# Adafruit_Metro_RP2040.net
KiCad netlist of a schematic drawn in EAGLE
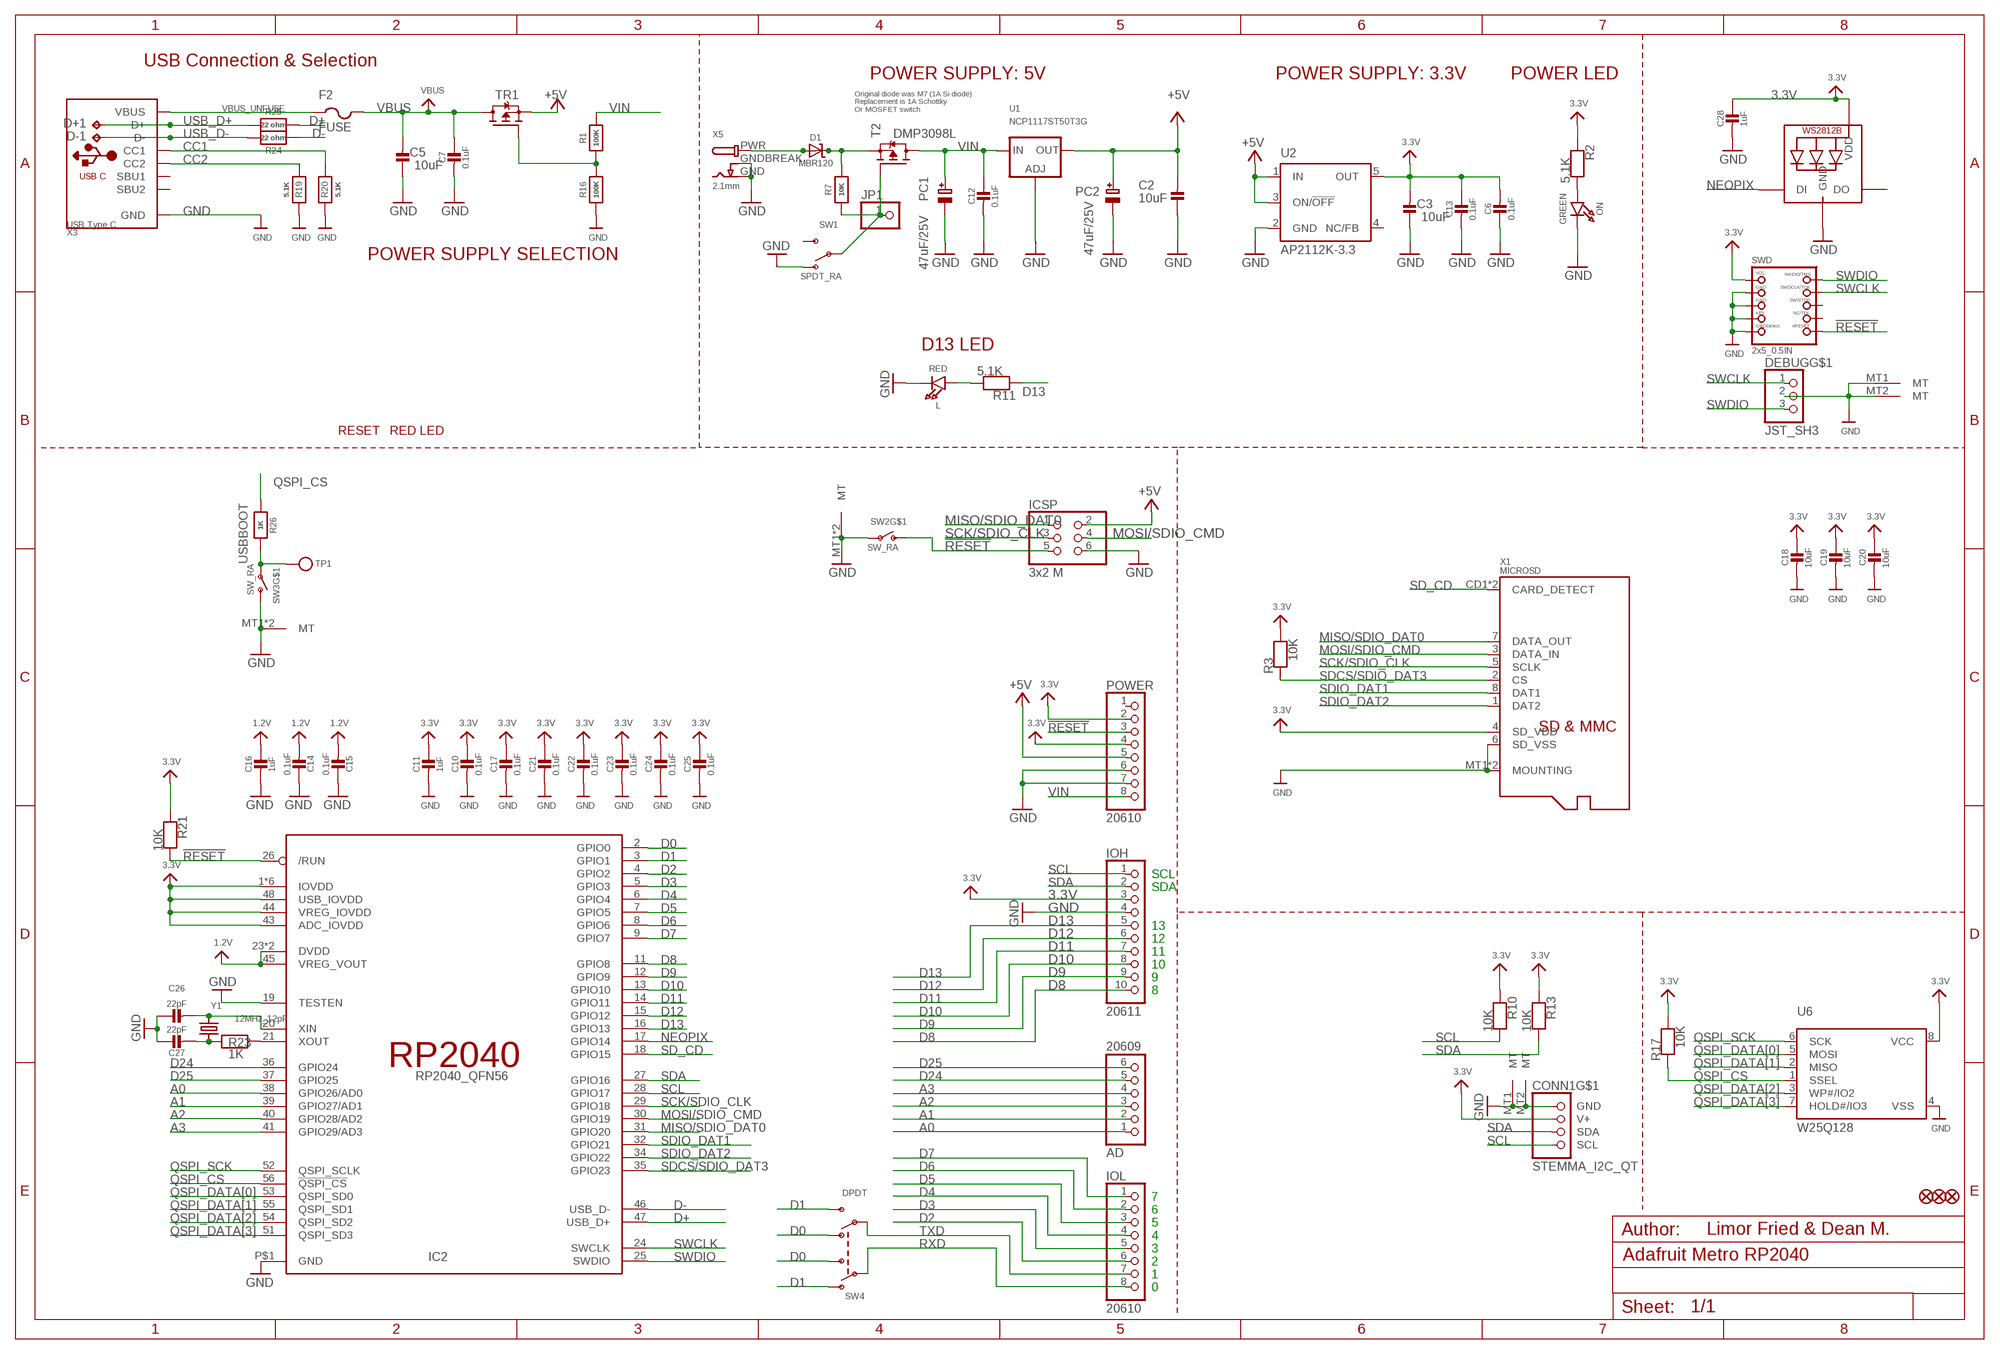
[diagram p0: schematic, sheet 1]

(export (version "E")
  (design (tool "Eeschema 10.0.6"))
  (components
    (comp (ref "AD")
      (value "20609")
      (footprint "eagle-import:1X06_OVALWAVE")
      (libsource (lib "eagle-import") (part "HEADER-1X6OVALWAVE"))
    )
    (comp (ref "C2")
      (value "10uF")
      (footprint "eagle-import:0805-NO")
      (libsource (lib "eagle-import") (part "CAP_CERAMIC0805-NOOUTLINE"))
    )
    (comp (ref "C3")
      (value "10uF")
      (footprint "eagle-import:0805-NO")
      (libsource (lib "eagle-import") (part "CAP_CERAMIC0805-NOOUTLINE"))
    )
    (comp (ref "C5")
      (value "10uF")
      (footprint "eagle-import:0805-NO")
      (libsource (lib "eagle-import") (part "CAP_CERAMIC0805-NOOUTLINE"))
    )
    (comp (ref "C6")
      (value "0.1uF")
      (footprint "eagle-import:0603-NO")
      (libsource (lib "eagle-import") (part "CAP_CERAMIC0603_NO"))
    )
    (comp (ref "C7")
      (value "0.1uF")
      (footprint "eagle-import:0603-NO")
      (libsource (lib "eagle-import") (part "CAP_CERAMIC0603_NO"))
    )
    (comp (ref "C10")
      (value "0.1uF")
      (footprint "eagle-import:0603-NO")
      (libsource (lib "eagle-import") (part "CAP_CERAMIC0603_NO"))
    )
    (comp (ref "C11")
      (value "1uF")
      (footprint "eagle-import:0603-NO")
      (libsource (lib "eagle-import") (part "CAP_CERAMIC0603_NO"))
    )
    (comp (ref "C12")
      (value "0.1uF")
      (footprint "eagle-import:0603-NO")
      (libsource (lib "eagle-import") (part "CAP_CERAMIC0603_NO"))
    )
    (comp (ref "C13")
      (value "0.1uF")
      (footprint "eagle-import:0603-NO")
      (libsource (lib "eagle-import") (part "CAP_CERAMIC0603_NO"))
    )
    (comp (ref "C14")
      (value "0.1uF")
      (footprint "eagle-import:0603-NO")
      (libsource (lib "eagle-import") (part "CAP_CERAMIC0603_NO"))
    )
    (comp (ref "C15")
      (value "0.1uF")
      (footprint "eagle-import:0603-NO")
      (libsource (lib "eagle-import") (part "CAP_CERAMIC0603_NO"))
    )
    (comp (ref "C16")
      (value "1uF")
      (footprint "eagle-import:0603-NO")
      (libsource (lib "eagle-import") (part "CAP_CERAMIC0603_NO"))
    )
    (comp (ref "C17")
      (value "0.1uF")
      (footprint "eagle-import:0603-NO")
      (libsource (lib "eagle-import") (part "CAP_CERAMIC0603_NO"))
    )
    (comp (ref "C18")
      (value "10uF")
      (footprint "eagle-import:0805-NO")
      (libsource (lib "eagle-import") (part "CAP_CERAMIC0805-NOOUTLINE"))
    )
    (comp (ref "C19")
      (value "10uF")
      (footprint "eagle-import:0805-NO")
      (libsource (lib "eagle-import") (part "CAP_CERAMIC0805-NOOUTLINE"))
    )
    (comp (ref "C20")
      (value "10uF")
      (footprint "eagle-import:0805-NO")
      (libsource (lib "eagle-import") (part "CAP_CERAMIC0805-NOOUTLINE"))
    )
    (comp (ref "C21")
      (value "0.1uF")
      (footprint "eagle-import:0603-NO")
      (libsource (lib "eagle-import") (part "CAP_CERAMIC0603_NO"))
    )
    (comp (ref "C22")
      (value "0.1uF")
      (footprint "eagle-import:0603-NO")
      (libsource (lib "eagle-import") (part "CAP_CERAMIC0603_NO"))
    )
    (comp (ref "C23")
      (value "0.1uF")
      (footprint "eagle-import:0603-NO")
      (libsource (lib "eagle-import") (part "CAP_CERAMIC0603_NO"))
    )
    (comp (ref "C24")
      (value "0.1uF")
      (footprint "eagle-import:0603-NO")
      (libsource (lib "eagle-import") (part "CAP_CERAMIC0603_NO"))
    )
    (comp (ref "C25")
      (value "0.1uF")
      (footprint "eagle-import:0603-NO")
      (libsource (lib "eagle-import") (part "CAP_CERAMIC0603_NO"))
    )
    (comp (ref "C26")
      (value "22pF")
      (footprint "eagle-import:0603-NO")
      (libsource (lib "eagle-import") (part "CAP_CERAMIC0603_NO"))
    )
    (comp (ref "C27")
      (value "22pF")
      (footprint "eagle-import:0603-NO")
      (libsource (lib "eagle-import") (part "CAP_CERAMIC0603_NO"))
    )
    (comp (ref "C28")
      (value "1uF")
      (footprint "eagle-import:0603-NO")
      (libsource (lib "eagle-import") (part "CAP_CERAMIC0603_NO"))
    )
    (comp (ref "CONN1")
      (value "STEMMA_I2C_QT")
      (footprint "eagle-import:JST_SH4")
      (libsource (lib "eagle-import") (part "STEMMA_I2C_QT"))
    )
    (comp (ref "D+1")
      (value "TPB1,27")
      (footprint "eagle-import:B1,27")
      (libsource (lib "eagle-import") (part "TPB1,27"))
    )
    (comp (ref "D-1")
      (value "TPB1,27")
      (footprint "eagle-import:B1,27")
      (libsource (lib "eagle-import") (part "TPB1,27"))
    )
    (comp (ref "D1")
      (value "MBR120")
      (footprint "eagle-import:SOD-123")
      (libsource (lib "eagle-import") (part "DIODE-SCHOTTKYSOD-123"))
    )
    (comp (ref "DEBUG")
      (value "JST_SH3")
      (footprint "eagle-import:JST_SH3")
      (libsource (lib "eagle-import") (part "CON_JST_SH_3PINSH"))
    )
    (comp (ref "F2")
      (value "FUSE")
      (footprint "eagle-import:R1206")
      (libsource (lib "eagle-import") (part "PTCFUSE-1206"))
    )
    (comp (ref "FD1")
      (value "FIDUCIAL_1MM")
      (footprint "eagle-import:FIDUCIAL_1MM")
      (libsource (lib "eagle-import") (part "FIDUCIAL_1MM"))
    )
    (comp (ref "FD2")
      (value "FIDUCIAL_1MM")
      (footprint "eagle-import:FIDUCIAL_1MM")
      (libsource (lib "eagle-import") (part "FIDUCIAL_1MM"))
    )
    (comp (ref "FD3")
      (value "FIDUCIAL_1MM")
      (footprint "eagle-import:FIDUCIAL_1MM")
      (libsource (lib "eagle-import") (part "FIDUCIAL_1MM"))
    )
    (comp (ref "IC2")
      (value "RP2040_QFN56")
      (footprint "eagle-import:QFN56_7MM_REDUCEDEPAD")
      (libsource (lib "eagle-import") (part "RP2040_QFN56"))
    )
    (comp (ref "ICSP")
      (value "3x2 M")
      (footprint "eagle-import:2X03_ROUND_70MIL")
      (libsource (lib "eagle-import") (part "HEADER-2X3"))
    )
    (comp (ref "IOH")
      (value "20611")
      (footprint "eagle-import:1X10_OVALWAVE")
      (libsource (lib "eagle-import") (part "HEADER-1X10OVALWAVE"))
    )
    (comp (ref "IOL")
      (value "20610")
      (footprint "eagle-import:1X08_OVALWAVE")
      (libsource (lib "eagle-import") (part "HEADER-1X8OVALWAVE"))
    )
    (comp (ref "JP1")
      (value "HEADER-1X1ROUND")
      (footprint "eagle-import:1X01_ROUND")
      (libsource (lib "eagle-import") (part "HEADER-1X1ROUND"))
    )
    (comp (ref "L")
      (value "RED")
      (footprint "eagle-import:CHIPLED_0603_NOOUTLINE")
      (libsource (lib "eagle-import") (part "LED0603_NOOUTLINE"))
    )
    (comp (ref "LED2")
      (value "WS2812B_3535FULL")
      (footprint "eagle-import:LED3535_FULLPADS")
      (libsource (lib "eagle-import") (part "WS2812B_3535FULL"))
    )
    (comp (ref "ON")
      (value "GREEN")
      (footprint "eagle-import:CHIPLED_0603_NOOUTLINE")
      (libsource (lib "eagle-import") (part "LED0603_NOOUTLINE"))
    )
    (comp (ref "PC1")
      (value "47uF/25V")
      (footprint "eagle-import:PANASONIC_D")
      (libsource (lib "eagle-import") (part "CAP_ELECTROLYTICPANASONIC_D"))
    )
    (comp (ref "PC2")
      (value "47uF/25V")
      (footprint "eagle-import:PANASONIC_D")
      (libsource (lib "eagle-import") (part "CAP_ELECTROLYTICPANASONIC_D"))
    )
    (comp (ref "POWER")
      (value "20610")
      (footprint "eagle-import:1X08_OVALWAVE")
      (libsource (lib "eagle-import") (part "HEADER-1X8OVALWAVE"))
    )
    (comp (ref "R1")
      (value "100K")
      (footprint "eagle-import:0603-NO")
      (libsource (lib "eagle-import") (part "RESISTOR_0603_NOOUT"))
    )
    (comp (ref "R2")
      (value "5.1K")
      (footprint "eagle-import:0603-NO")
      (libsource (lib "eagle-import") (part "RESISTOR_0603_NOOUT"))
    )
    (comp (ref "R3")
      (value "10K")
      (footprint "eagle-import:0603-NO")
      (libsource (lib "eagle-import") (part "RESISTOR_0603_NOOUT"))
    )
    (comp (ref "R7")
      (value "10K")
      (footprint "eagle-import:0603-NO")
      (libsource (lib "eagle-import") (part "RESISTOR_0603_NOOUT"))
    )
    (comp (ref "R10")
      (value "10K")
      (footprint "eagle-import:0603-NO")
      (libsource (lib "eagle-import") (part "RESISTOR_0603_NOOUT"))
    )
    (comp (ref "R11")
      (value "5.1K")
      (footprint "eagle-import:0603-NO")
      (libsource (lib "eagle-import") (part "RESISTOR_0603_NOOUT"))
    )
    (comp (ref "R13")
      (value "10K")
      (footprint "eagle-import:0603-NO")
      (libsource (lib "eagle-import") (part "RESISTOR_0603_NOOUT"))
    )
    (comp (ref "R16")
      (value "100K")
      (footprint "eagle-import:0603-NO")
      (libsource (lib "eagle-import") (part "RESISTOR_0603_NOOUT"))
    )
    (comp (ref "R17")
      (value "10K")
      (footprint "eagle-import:0603-NO")
      (libsource (lib "eagle-import") (part "RESISTOR_0603_NOOUT"))
    )
    (comp (ref "R19")
      (value "5.1K")
      (footprint "eagle-import:0603-NO")
      (libsource (lib "eagle-import") (part "RESISTOR_0603_NOOUT"))
    )
    (comp (ref "R20")
      (value "5.1K")
      (footprint "eagle-import:0603-NO")
      (libsource (lib "eagle-import") (part "RESISTOR_0603_NOOUT"))
    )
    (comp (ref "R21")
      (value "10K")
      (footprint "eagle-import:0603-NO")
      (libsource (lib "eagle-import") (part "RESISTOR_0603_NOOUT"))
    )
    (comp (ref "R23")
      (value "1K")
      (footprint "eagle-import:0603-NO")
      (libsource (lib "eagle-import") (part "RESISTOR_0603_NOOUT"))
    )
    (comp (ref "R24")
      (value "22 ohm")
      (footprint "eagle-import:0603-NO")
      (libsource (lib "eagle-import") (part "RESISTOR_0603_NOOUT"))
    )
    (comp (ref "R25")
      (value "22 ohm")
      (footprint "eagle-import:0603-NO")
      (libsource (lib "eagle-import") (part "RESISTOR_0603_NOOUT"))
    )
    (comp (ref "R26")
      (value "1K")
      (footprint "eagle-import:0603-NO")
      (libsource (lib "eagle-import") (part "RESISTOR_0603_NOOUT"))
    )
    (comp (ref "SW1")
      (value "SPDT_RA")
      (footprint "eagle-import:SPDT_SMT_SSSS811101")
      (libsource (lib "eagle-import") (part "SWITCH_SPDT"))
    )
    (comp (ref "SW2")
      (value "SW_RA")
      (footprint "eagle-import:SPST_TACTILE_RA")
      (libsource (lib "eagle-import") (part "SWITCH_SPST_MNT_TACT_RA"))
    )
    (comp (ref "SW3")
      (value "SW_RA")
      (footprint "eagle-import:SPST_TACTILE_RA")
      (libsource (lib "eagle-import") (part "SWITCH_SPST_MNT_TACT_RA"))
    )
    (comp (ref "SW4")
      (value "DPDT")
      (footprint "eagle-import:EG1390")
      (libsource (lib "eagle-import") (part "SWITCH_DPDTEG1390"))
    )
    (comp (ref "SWD")
      (value "2x5_0.5IN")
      (footprint "eagle-import:2X05_1.27MM_BOX_POSTS")
      (libsource (lib "eagle-import") (part "JTAG-CORTEXBOXPOSTS"))
    )
    (comp (ref "T2")
      (value "DMP3098L")
      (footprint "eagle-import:SOT23-WIDE")
      (libsource (lib "eagle-import") (part "MOSFET-PWIDE"))
    )
    (comp (ref "TP1")
      (value "TESTPOINTROUND1.5MMNO")
      (footprint "eagle-import:TESTPOINT_ROUND_1.5MM_NO")
      (libsource (lib "eagle-import") (part "TESTPOINTROUND1.5MMNO"))
    )
    (comp (ref "TR1")
      (value "DMP3098L")
      (footprint "eagle-import:SOT23-WIDE")
      (libsource (lib "eagle-import") (part "MOSFET-PWIDE"))
    )
    (comp (ref "U1")
      (value "NCP1117ST50T3G")
      (footprint "eagle-import:SOT223-R")
      (libsource (lib "eagle-import") (part "LM1117SOT223-REFLOW"))
    )
    (comp (ref "U2")
      (value "AP2112K-3.3")
      (footprint "eagle-import:SOT23-DBV")
      (libsource (lib "eagle-import") (part "LP2985-XXDBVR33"))
    )
    (comp (ref "U6")
      (value "W25Q128")
      (footprint "eagle-import:SOIC8_208MIL")
      (libsource (lib "eagle-import") (part "SPIFLASH_8PIN208MIL"))
    )
    (comp (ref "X1")
      (value "MICROSD")
      (footprint "eagle-import:MICROSD")
      (libsource (lib "eagle-import") (part "MICROSD"))
    )
    (comp (ref "X3")
      (value "USB Type C")
      (footprint "eagle-import:USB_C_CUSB31-CFM2AX-01-X")
      (libsource (lib "eagle-import") (part "USB_C"))
    )
    (comp (ref "X5")
      (value "2.1mm")
      (footprint "eagle-import:DCJACK_2MM_PTH")
      (libsource (lib "eagle-import") (part "DCBARRELPTH"))
    )
    (comp (ref "Y1")
      (value "12MHz_12pF")
      (footprint "eagle-import:CRYSTAL_2.5X2")
      (libsource (lib "eagle-import") (part "CRYSTAL2.5X2.0"))
    )
  )
  (nets
    (net (code "1") (name "+5V") (class "Default")
      (node (ref "C2") (pin "2") (pinfunction "2_2") (pintype "passive"))
      (node (ref "ICSP") (pin "2") (pinfunction "2_2") (pintype "passive"))
      (node (ref "PC2") (pin "+") (pinfunction "+_+") (pintype "passive"))
      (node (ref "POWER") (pin "5") (pinfunction "5_5") (pintype "passive"))
      (node (ref "TR1") (pin "2") (pinfunction "S_2") (pintype "passive"))
      (node (ref "U1") (pin "2") (pinfunction "OUT_2") (pintype "passive"))
      (node (ref "U1") (pin "4") (pinfunction "OUT_4") (pintype "passive"))
      (node (ref "U2") (pin "1") (pinfunction "IN_1") (pintype "input"))
      (node (ref "U2") (pin "3") (pinfunction "ON/~{OFF}_3") (pintype "input"))
    )
    (net (code "2") (name "/A0") (class "Default")
      (node (ref "AD") (pin "1") (pinfunction "1_1") (pintype "passive"))
      (node (ref "IC2") (pin "38") (pinfunction "GPIO26/AD0_38") (pintype "bidirectional"))
    )
    (net (code "3") (name "/A1") (class "Default")
      (node (ref "AD") (pin "2") (pinfunction "2_2") (pintype "passive"))
      (node (ref "IC2") (pin "39") (pinfunction "GPIO27/AD1_39") (pintype "bidirectional"))
    )
    (net (code "4") (name "/A2") (class "Default")
      (node (ref "AD") (pin "3") (pinfunction "3_3") (pintype "passive"))
      (node (ref "IC2") (pin "40") (pinfunction "GPIO28/AD2_40") (pintype "bidirectional"))
    )
    (net (code "5") (name "/A3") (class "Default")
      (node (ref "AD") (pin "4") (pinfunction "4_4") (pintype "passive"))
      (node (ref "IC2") (pin "41") (pinfunction "GPIO29/AD3_41") (pintype "bidirectional"))
    )
    (net (code "6") (name "/CC1") (class "Default")
      (node (ref "R20") (pin "2") (pinfunction "2_2") (pintype "passive"))
      (node (ref "X3") (pin "A5") (pinfunction "CC1_A5") (pintype "bidirectional"))
    )
    (net (code "7") (name "/CC2") (class "Default")
      (node (ref "R19") (pin "2") (pinfunction "2_2") (pintype "passive"))
      (node (ref "X3") (pin "B5") (pinfunction "CC2_B5") (pintype "bidirectional"))
    )
    (net (code "8") (name "/D+") (class "Default")
      (node (ref "IC2") (pin "47") (pinfunction "USB_D+_47") (pintype "bidirectional"))
      (node (ref "R25") (pin "2") (pinfunction "2_2") (pintype "passive"))
    )
    (net (code "9") (name "/D-") (class "Default")
      (node (ref "IC2") (pin "46") (pinfunction "USB_D-_46") (pintype "bidirectional"))
      (node (ref "R24") (pin "2") (pinfunction "2_2") (pintype "passive"))
    )
    (net (code "10") (name "/D0") (class "Default")
      (node (ref "IC2") (pin "2") (pinfunction "GPIO0_2") (pintype "bidirectional"))
      (node (ref "SW4") (pin "O2") (pinfunction "O2_O2") (pintype "passive"))
      (node (ref "SW4") (pin "S1") (pinfunction "S1_S1") (pintype "passive"))
    )
    (net (code "11") (name "/D1") (class "Default")
      (node (ref "IC2") (pin "3") (pinfunction "GPIO1_3") (pintype "bidirectional"))
      (node (ref "SW4") (pin "O1") (pinfunction "O1_O1") (pintype "passive"))
      (node (ref "SW4") (pin "S2") (pinfunction "S2_S2") (pintype "passive"))
    )
    (net (code "12") (name "/D2") (class "Default")
      (node (ref "IC2") (pin "4") (pinfunction "GPIO2_4") (pintype "bidirectional"))
      (node (ref "IOL") (pin "6") (pinfunction "6_6") (pintype "passive"))
    )
    (net (code "13") (name "/D3") (class "Default")
      (node (ref "IC2") (pin "5") (pinfunction "GPIO3_5") (pintype "bidirectional"))
      (node (ref "IOL") (pin "5") (pinfunction "5_5") (pintype "passive"))
    )
    (net (code "14") (name "/D4") (class "Default")
      (node (ref "IC2") (pin "6") (pinfunction "GPIO4_6") (pintype "bidirectional"))
      (node (ref "IOL") (pin "4") (pinfunction "4_4") (pintype "passive"))
    )
    (net (code "15") (name "/D5") (class "Default")
      (node (ref "IC2") (pin "7") (pinfunction "GPIO5_7") (pintype "bidirectional"))
      (node (ref "IOL") (pin "3") (pinfunction "3_3") (pintype "passive"))
    )
    (net (code "16") (name "/D6") (class "Default")
      (node (ref "IC2") (pin "8") (pinfunction "GPIO6_8") (pintype "bidirectional"))
      (node (ref "IOL") (pin "2") (pinfunction "2_2") (pintype "passive"))
    )
    (net (code "17") (name "/D7") (class "Default")
      (node (ref "IC2") (pin "9") (pinfunction "GPIO7_9") (pintype "bidirectional"))
      (node (ref "IOL") (pin "1") (pinfunction "1_1") (pintype "passive"))
    )
    (net (code "18") (name "/D8") (class "Default")
      (node (ref "IC2") (pin "11") (pinfunction "GPIO8_11") (pintype "bidirectional"))
      (node (ref "IOH") (pin "10") (pinfunction "10_10") (pintype "passive"))
    )
    (net (code "19") (name "/D9") (class "Default")
      (node (ref "IC2") (pin "12") (pinfunction "GPIO9_12") (pintype "bidirectional"))
      (node (ref "IOH") (pin "9") (pinfunction "9_9") (pintype "passive"))
    )
    (net (code "20") (name "/D10") (class "Default")
      (node (ref "IC2") (pin "13") (pinfunction "GPIO10_13") (pintype "bidirectional"))
      (node (ref "IOH") (pin "8") (pinfunction "8_8") (pintype "passive"))
    )
    (net (code "21") (name "/D11") (class "Default")
      (node (ref "IC2") (pin "14") (pinfunction "GPIO11_14") (pintype "bidirectional"))
      (node (ref "IOH") (pin "7") (pinfunction "7_7") (pintype "passive"))
    )
    (net (code "22") (name "/D12") (class "Default")
      (node (ref "IC2") (pin "15") (pinfunction "GPIO12_15") (pintype "bidirectional"))
      (node (ref "IOH") (pin "6") (pinfunction "6_6") (pintype "passive"))
    )
    (net (code "23") (name "/D13") (class "Default")
      (node (ref "IC2") (pin "16") (pinfunction "GPIO13_16") (pintype "bidirectional"))
      (node (ref "IOH") (pin "5") (pinfunction "5_5") (pintype "passive"))
      (node (ref "R11") (pin "1") (pinfunction "1_1") (pintype "passive"))
    )
    (net (code "24") (name "/D24") (class "Default")
      (node (ref "AD") (pin "5") (pinfunction "5_5") (pintype "passive"))
      (node (ref "IC2") (pin "36") (pinfunction "GPIO24_36") (pintype "bidirectional"))
    )
    (net (code "25") (name "/D25") (class "Default")
      (node (ref "AD") (pin "6") (pinfunction "6_6") (pintype "passive"))
      (node (ref "IC2") (pin "37") (pinfunction "GPIO25_37") (pintype "bidirectional"))
    )
    (net (code "26") (name "/MISO{slash}SDIO_DAT0") (class "Default")
      (node (ref "IC2") (pin "31") (pinfunction "GPIO20_31") (pintype "bidirectional"))
      (node (ref "ICSP") (pin "1") (pinfunction "1_1") (pintype "passive"))
      (node (ref "X1") (pin "7") (pinfunction "DATA_OUT_7") (pintype "output"))
    )
    (net (code "27") (name "/MOSI{slash}SDIO_CMD") (class "Default")
      (node (ref "IC2") (pin "30") (pinfunction "GPIO19_30") (pintype "bidirectional"))
      (node (ref "ICSP") (pin "4") (pinfunction "4_4") (pintype "passive"))
      (node (ref "X1") (pin "3") (pinfunction "DATA_IN_3") (pintype "input"))
    )
    (net (code "28") (name "/NEOPIX") (class "Default")
      (node (ref "IC2") (pin "17") (pinfunction "GPIO14_17") (pintype "bidirectional"))
      (node (ref "LED2") (pin "1") (pinfunction "DI_1") (pintype "input"))
    )
    (net (code "29") (name "/QSPI_CS") (class "Default")
      (node (ref "IC2") (pin "56") (pinfunction "~{QSPI_CS}_56") (pintype "bidirectional"))
      (node (ref "R17") (pin "1") (pinfunction "1_1") (pintype "passive"))
      (node (ref "R26") (pin "1") (pinfunction "1_1") (pintype "passive"))
      (node (ref "U6") (pin "1") (pinfunction "SSEL_1") (pintype "bidirectional"))
    )
    (net (code "30") (name "/QSPI_DATA[0]") (class "Default")
      (node (ref "IC2") (pin "53") (pinfunction "QSPI_SD0_53") (pintype "bidirectional"))
      (node (ref "U6") (pin "5") (pinfunction "MOSI_5") (pintype "bidirectional"))
    )
    (net (code "31") (name "/QSPI_DATA[1]") (class "Default")
      (node (ref "IC2") (pin "55") (pinfunction "QSPI_SD1_55") (pintype "bidirectional"))
      (node (ref "U6") (pin "2") (pinfunction "MISO_2") (pintype "bidirectional"))
    )
    (net (code "32") (name "/QSPI_DATA[2]") (class "Default")
      (node (ref "IC2") (pin "54") (pinfunction "QSPI_SD2_54") (pintype "bidirectional"))
      (node (ref "U6") (pin "3") (pinfunction "WP#/IO2_3") (pintype "bidirectional"))
    )
    (net (code "33") (name "/QSPI_DATA[3]") (class "Default")
      (node (ref "IC2") (pin "51") (pinfunction "QSPI_SD3_51") (pintype "bidirectional"))
      (node (ref "U6") (pin "7") (pinfunction "HOLD#/IO3_7") (pintype "bidirectional"))
    )
    (net (code "34") (name "/QSPI_SCK") (class "Default")
      (node (ref "IC2") (pin "52") (pinfunction "QSPI_SCLK_52") (pintype "bidirectional"))
      (node (ref "U6") (pin "6") (pinfunction "SCK_6") (pintype "bidirectional"))
    )
    (net (code "35") (name "/RXD") (class "Default")
      (node (ref "IOL") (pin "8") (pinfunction "8_8") (pintype "passive"))
      (node (ref "SW4") (pin "P1") (pinfunction "P1_P1") (pintype "passive"))
    )
    (net (code "36") (name "/SCK{slash}SDIO_CLK") (class "Default")
      (node (ref "IC2") (pin "29") (pinfunction "GPIO18_29") (pintype "bidirectional"))
      (node (ref "ICSP") (pin "3") (pinfunction "3_3") (pintype "passive"))
      (node (ref "X1") (pin "5") (pinfunction "SCLK_5") (pintype "input"))
    )
    (net (code "37") (name "/SCL") (class "Default")
      (node (ref "CONN1") (pin "4") (pinfunction "SCL_4") (pintype "passive"))
      (node (ref "IC2") (pin "28") (pinfunction "GPIO17_28") (pintype "bidirectional"))
      (node (ref "IOH") (pin "1") (pinfunction "1_1") (pintype "passive"))
      (node (ref "R10") (pin "2") (pinfunction "2_2") (pintype "passive"))
    )
    (net (code "38") (name "/SDA") (class "Default")
      (node (ref "CONN1") (pin "3") (pinfunction "SDA_3") (pintype "passive"))
      (node (ref "IC2") (pin "27") (pinfunction "GPIO16_27") (pintype "bidirectional"))
      (node (ref "IOH") (pin "2") (pinfunction "2_2") (pintype "passive"))
      (node (ref "R13") (pin "2") (pinfunction "2_2") (pintype "passive"))
    )
    (net (code "39") (name "/SDCS{slash}SDIO_DAT3") (class "Default")
      (node (ref "IC2") (pin "35") (pinfunction "GPIO23_35") (pintype "bidirectional"))
      (node (ref "R3") (pin "1") (pinfunction "1_1") (pintype "passive"))
      (node (ref "X1") (pin "2") (pinfunction "CS_2") (pintype "input"))
    )
    (net (code "40") (name "/SDIO_DAT1") (class "Default")
      (node (ref "IC2") (pin "32") (pinfunction "GPIO21_32") (pintype "bidirectional"))
      (node (ref "X1") (pin "8") (pinfunction "DAT1_8") (pintype "bidirectional"))
    )
    (net (code "41") (name "/SDIO_DAT2") (class "Default")
      (node (ref "IC2") (pin "34") (pinfunction "GPIO22_34") (pintype "bidirectional"))
      (node (ref "X1") (pin "1") (pinfunction "DAT2_1") (pintype "bidirectional"))
    )
    (net (code "42") (name "/SD_CD") (class "Default")
      (node (ref "IC2") (pin "18") (pinfunction "GPIO15_18") (pintype "bidirectional"))
      (node (ref "X1") (pin "CD1") (pinfunction "CARD_DETECT_CD1") (pintype "passive"))
      (node (ref "X1") (pin "CD2") (pinfunction "CARD_DETECT_CD2") (pintype "passive"))
    )
    (net (code "43") (name "/SWCLK") (class "Default")
      (node (ref "DEBUG") (pin "1") (pinfunction "1_1") (pintype "passive"))
      (node (ref "IC2") (pin "24") (pinfunction "SWCLK_24") (pintype "bidirectional"))
      (node (ref "SWD") (pin "4") (pinfunction "SWDCLK_4") (pintype "bidirectional"))
    )
    (net (code "44") (name "/SWDIO") (class "Default")
      (node (ref "DEBUG") (pin "3") (pinfunction "3_3") (pintype "passive"))
      (node (ref "IC2") (pin "25") (pinfunction "SWDIO_25") (pintype "bidirectional"))
      (node (ref "SWD") (pin "2") (pinfunction "SWDIO_2") (pintype "bidirectional"))
    )
    (net (code "45") (name "/TXD") (class "Default")
      (node (ref "IOL") (pin "7") (pinfunction "7_7") (pintype "passive"))
      (node (ref "SW4") (pin "P2") (pinfunction "P2_P2") (pintype "passive"))
    )
    (net (code "46") (name "/USBBOOT") (class "Default")
      (node (ref "R26") (pin "2") (pinfunction "2_2") (pintype "passive"))
      (node (ref "SW3") (pin "1") (pinfunction "P_1") (pintype "passive"))
      (node (ref "TP1") (pin "P$1") (pinfunction "P$1_P$1") (pintype "bidirectional"))
    )
    (net (code "47") (name "/USB_D+") (class "Default")
      (node (ref "D+1") (pin "TP") (pinfunction "TP_TP") (pintype "input"))
      (node (ref "R25") (pin "1") (pinfunction "1_1") (pintype "passive"))
      (node (ref "X3") (pin "A6") (pinfunction "D+_A6") (pintype "bidirectional"))
      (node (ref "X3") (pin "B6") (pinfunction "D+_B6") (pintype "bidirectional"))
    )
    (net (code "48") (name "/USB_D-") (class "Default")
      (node (ref "D-1") (pin "TP") (pinfunction "TP_TP") (pintype "input"))
      (node (ref "R24") (pin "1") (pinfunction "1_1") (pintype "passive"))
      (node (ref "X3") (pin "A7") (pinfunction "D-_A7") (pintype "bidirectional"))
      (node (ref "X3") (pin "B7") (pinfunction "D-_B7") (pintype "bidirectional"))
    )
    (net (code "49") (name "/VBUS_UNFUSE") (class "Default")
      (node (ref "F2") (pin "1") (pinfunction "1_1") (pintype "passive"))
      (node (ref "X3") (pin "A4B9") (pinfunction "VBUS_A4B9") (pintype "power_in"))
      (node (ref "X3") (pin "B4A9") (pinfunction "VBUS_B4A9") (pintype "power_in"))
    )
    (net (code "50") (name "/VIN") (class "Default")
      (node (ref "C12") (pin "1") (pinfunction "1_1") (pintype "passive"))
      (node (ref "PC1") (pin "+") (pinfunction "+_+") (pintype "passive"))
      (node (ref "POWER") (pin "8") (pinfunction "8_8") (pintype "passive"))
      (node (ref "R1") (pin "2") (pinfunction "2_2") (pintype "passive"))
      (node (ref "T2") (pin "3") (pinfunction "D_3") (pintype "passive"))
      (node (ref "U1") (pin "3") (pinfunction "IN_3") (pintype "input"))
    )
    (net (code "51") (name "/~{RESET}") (class "Default")
      (node (ref "IC2") (pin "26") (pinfunction "/RUN_26") (pintype "bidirectional"))
      (node (ref "ICSP") (pin "5") (pinfunction "5_5") (pintype "passive"))
      (node (ref "POWER") (pin "3") (pinfunction "3_3") (pintype "passive"))
      (node (ref "R21") (pin "2") (pinfunction "2_2") (pintype "passive"))
      (node (ref "SW2") (pin "2") (pinfunction "S_2") (pintype "passive"))
      (node (ref "SWD") (pin "10") (pinfunction "NRESET_10") (pintype "bidirectional"))
    )
    (net (code "52") (name "1.2V") (class "Default")
      (node (ref "C14") (pin "2") (pinfunction "2_2") (pintype "passive"))
      (node (ref "C15") (pin "2") (pinfunction "2_2") (pintype "passive"))
      (node (ref "C16") (pin "1") (pinfunction "1_1") (pintype "passive"))
      (node (ref "IC2") (pin "23") (pinfunction "DVDD_23") (pintype "power_in"))
      (node (ref "IC2") (pin "45") (pinfunction "VREG_VOUT_45") (pintype "power_in"))
      (node (ref "IC2") (pin "50") (pinfunction "DVDD_50") (pintype "power_in"))
    )
    (net (code "53") (name "3.3V") (class "Default")
      (node (ref "C10") (pin "1") (pinfunction "1_1") (pintype "passive"))
      (node (ref "C11") (pin "1") (pinfunction "1_1") (pintype "passive"))
      (node (ref "C13") (pin "1") (pinfunction "1_1") (pintype "passive"))
      (node (ref "C17") (pin "1") (pinfunction "1_1") (pintype "passive"))
      (node (ref "C18") (pin "1") (pinfunction "1_1") (pintype "passive"))
      (node (ref "C19") (pin "1") (pinfunction "1_1") (pintype "passive"))
      (node (ref "C20") (pin "1") (pinfunction "1_1") (pintype "passive"))
      (node (ref "C21") (pin "1") (pinfunction "1_1") (pintype "passive"))
      (node (ref "C22") (pin "1") (pinfunction "1_1") (pintype "passive"))
      (node (ref "C23") (pin "1") (pinfunction "1_1") (pintype "passive"))
      (node (ref "C24") (pin "1") (pinfunction "1_1") (pintype "passive"))
      (node (ref "C25") (pin "1") (pinfunction "1_1") (pintype "passive"))
      (node (ref "C28") (pin "1") (pinfunction "1_1") (pintype "passive"))
      (node (ref "C3") (pin "2") (pinfunction "2_2") (pintype "passive"))
      (node (ref "C6") (pin "2") (pinfunction "2_2") (pintype "passive"))
      (node (ref "CONN1") (pin "2") (pinfunction "V+_2") (pintype "passive"))
      (node (ref "IC2") (pin "1") (pinfunction "IOVDD_1") (pintype "power_in"))
      (node (ref "IC2") (pin "10") (pinfunction "IOVDD_10") (pintype "power_in"))
      (node (ref "IC2") (pin "22") (pinfunction "IOVDD_22") (pintype "power_in"))
      (node (ref "IC2") (pin "33") (pinfunction "IOVDD_33") (pintype "power_in"))
      (node (ref "IC2") (pin "42") (pinfunction "IOVDD_42") (pintype "power_in"))
      (node (ref "IC2") (pin "43") (pinfunction "ADC_IOVDD_43") (pintype "power_in"))
      (node (ref "IC2") (pin "44") (pinfunction "VREG_IOVDD_44") (pintype "power_in"))
      (node (ref "IC2") (pin "48") (pinfunction "USB_IOVDD_48") (pintype "power_in"))
      (node (ref "IC2") (pin "49") (pinfunction "IOVDD_49") (pintype "power_in"))
      (node (ref "IOH") (pin "3") (pinfunction "3_3") (pintype "passive"))
      (node (ref "LED2") (pin "2") (pinfunction "VDD_2") (pintype "power_in"))
      (node (ref "POWER") (pin "2") (pinfunction "2_2") (pintype "passive"))
      (node (ref "POWER") (pin "4") (pinfunction "4_4") (pintype "passive"))
      (node (ref "R10") (pin "1") (pinfunction "1_1") (pintype "passive"))
      (node (ref "R13") (pin "1") (pinfunction "1_1") (pintype "passive"))
      (node (ref "R17") (pin "2") (pinfunction "2_2") (pintype "passive"))
      (node (ref "R2") (pin "1") (pinfunction "1_1") (pintype "passive"))
      (node (ref "R21") (pin "1") (pinfunction "1_1") (pintype "passive"))
      (node (ref "R3") (pin "2") (pinfunction "2_2") (pintype "passive"))
      (node (ref "SWD") (pin "1") (pinfunction "VCC_1") (pintype "power_in"))
      (node (ref "U2") (pin "5") (pinfunction "OUT_5") (pintype "passive"))
      (node (ref "U6") (pin "8") (pinfunction "VCC_8") (pintype "bidirectional"))
      (node (ref "X1") (pin "4") (pinfunction "SD_VDD_4") (pintype "power_in"))
    )
    (net (code "54") (name "GND") (class "Default")
      (node (ref "C10") (pin "2") (pinfunction "2_2") (pintype "passive"))
      (node (ref "C11") (pin "2") (pinfunction "2_2") (pintype "passive"))
      (node (ref "C12") (pin "2") (pinfunction "2_2") (pintype "passive"))
      (node (ref "C13") (pin "2") (pinfunction "2_2") (pintype "passive"))
      (node (ref "C14") (pin "1") (pinfunction "1_1") (pintype "passive"))
      (node (ref "C15") (pin "1") (pinfunction "1_1") (pintype "passive"))
      (node (ref "C16") (pin "2") (pinfunction "2_2") (pintype "passive"))
      (node (ref "C17") (pin "2") (pinfunction "2_2") (pintype "passive"))
      (node (ref "C18") (pin "2") (pinfunction "2_2") (pintype "passive"))
      (node (ref "C19") (pin "2") (pinfunction "2_2") (pintype "passive"))
      (node (ref "C2") (pin "1") (pinfunction "1_1") (pintype "passive"))
      (node (ref "C20") (pin "2") (pinfunction "2_2") (pintype "passive"))
      (node (ref "C21") (pin "2") (pinfunction "2_2") (pintype "passive"))
      (node (ref "C22") (pin "2") (pinfunction "2_2") (pintype "passive"))
      (node (ref "C23") (pin "2") (pinfunction "2_2") (pintype "passive"))
      (node (ref "C24") (pin "2") (pinfunction "2_2") (pintype "passive"))
      (node (ref "C25") (pin "2") (pinfunction "2_2") (pintype "passive"))
      (node (ref "C26") (pin "1") (pinfunction "1_1") (pintype "passive"))
      (node (ref "C27") (pin "1") (pinfunction "1_1") (pintype "passive"))
      (node (ref "C28") (pin "2") (pinfunction "2_2") (pintype "passive"))
      (node (ref "C3") (pin "1") (pinfunction "1_1") (pintype "passive"))
      (node (ref "C5") (pin "1") (pinfunction "1_1") (pintype "passive"))
      (node (ref "C6") (pin "1") (pinfunction "1_1") (pintype "passive"))
      (node (ref "C7") (pin "2") (pinfunction "2_2") (pintype "passive"))
      (node (ref "CONN1") (pin "1") (pinfunction "GND_1") (pintype "passive"))
      (node (ref "CONN1") (pin "MT1") (pinfunction "MT_MT1") (pintype "bidirectional"))
      (node (ref "CONN1") (pin "MT2") (pinfunction "MT_MT2") (pintype "bidirectional"))
      (node (ref "DEBUG") (pin "2") (pinfunction "2_2") (pintype "passive"))
      (node (ref "DEBUG") (pin "MT1") (pinfunction "MT_MT1") (pintype "bidirectional"))
      (node (ref "DEBUG") (pin "MT2") (pinfunction "MT_MT2") (pintype "bidirectional"))
      (node (ref "IC2") (pin "19") (pinfunction "TESTEN_19") (pintype "input"))
      (node (ref "IC2") (pin "P$1") (pinfunction "GND_P$1") (pintype "power_in"))
      (node (ref "ICSP") (pin "6") (pinfunction "6_6") (pintype "passive"))
      (node (ref "IOH") (pin "4") (pinfunction "4_4") (pintype "passive"))
      (node (ref "L") (pin "C") (pinfunction "C_C") (pintype "passive"))
      (node (ref "LED2") (pin "4") (pinfunction "GND_4") (pintype "power_in"))
      (node (ref "ON") (pin "C") (pinfunction "C_C") (pintype "passive"))
      (node (ref "PC1") (pin "-") (pinfunction "-_-") (pintype "passive"))
      (node (ref "PC2") (pin "-") (pinfunction "-_-") (pintype "passive"))
      (node (ref "POWER") (pin "6") (pinfunction "6_6") (pintype "passive"))
      (node (ref "POWER") (pin "7") (pinfunction "7_7") (pintype "passive"))
      (node (ref "R16") (pin "1") (pinfunction "1_1") (pintype "passive"))
      (node (ref "R19") (pin "1") (pinfunction "1_1") (pintype "passive"))
      (node (ref "R20") (pin "1") (pinfunction "1_1") (pintype "passive"))
      (node (ref "SW1") (pin "A") (pinfunction "O_A") (pintype "passive"))
      (node (ref "SW2") (pin "1") (pinfunction "P_1") (pintype "passive"))
      (node (ref "SW2") (pin "MT1") (pinfunction "MT_MT1") (pintype "bidirectional"))
      (node (ref "SW2") (pin "MT2") (pinfunction "MT_MT2") (pintype "bidirectional"))
      (node (ref "SW3") (pin "2") (pinfunction "S_2") (pintype "passive"))
      (node (ref "SW3") (pin "MT1") (pinfunction "MT_MT1") (pintype "bidirectional"))
      (node (ref "SW3") (pin "MT2") (pinfunction "MT_MT2") (pintype "bidirectional"))
      (node (ref "SWD") (pin "3") (pinfunction "GND_3") (pintype "power_in"))
      (node (ref "SWD") (pin "5") (pinfunction "GND_5") (pintype "power_in"))
      (node (ref "SWD") (pin "7") (pinfunction "KEY_7") (pintype "bidirectional"))
      (node (ref "SWD") (pin "9") (pinfunction "GNDDETECT_9") (pintype "bidirectional"))
      (node (ref "U1") (pin "1") (pinfunction "ADJ_1") (pintype "input"))
      (node (ref "U2") (pin "2") (pinfunction "GND_2") (pintype "power_in"))
      (node (ref "U6") (pin "4") (pinfunction "VSS_4") (pintype "bidirectional"))
      (node (ref "X1") (pin "6") (pinfunction "SD_VSS_6") (pintype "power_in"))
      (node (ref "X1") (pin "MT1") (pinfunction "MOUNTING_MT1") (pintype "passive"))
      (node (ref "X1") (pin "MT2") (pinfunction "MOUNTING_MT2") (pintype "passive"))
      (node (ref "X3") (pin "A1B12") (pinfunction "GND_A1B12") (pintype "power_in"))
      (node (ref "X3") (pin "B1A12") (pinfunction "GND_B1A12") (pintype "power_in"))
      (node (ref "X5") (pin "GND") (pinfunction "GND_GND") (pintype "power_in"))
      (node (ref "X5") (pin "GNDBREAK") (pinfunction "GNDBREAK_GNDBREAK") (pintype "power_in"))
    )
    (net (code "55") (name "Net-(C27-Pad2)") (class "Default")
      (node (ref "C27") (pin "2") (pinfunction "2_2") (pintype "passive"))
      (node (ref "R23") (pin "1") (pinfunction "1_1") (pintype "passive"))
      (node (ref "Y1") (pin "1") (pinfunction "1_1") (pintype "passive"))
    )
    (net (code "56") (name "Net-(D1-PadA)") (class "Default")
      (node (ref "D1") (pin "A") (pinfunction "A_A") (pintype "passive"))
      (node (ref "X5") (pin "PWR") (pinfunction "PWR_PWR") (pintype "power_in"))
    )
    (net (code "57") (name "Net-(IC2-XIN)") (class "Default")
      (node (ref "C26") (pin "2") (pinfunction "2_2") (pintype "passive"))
      (node (ref "IC2") (pin "20") (pinfunction "XIN_20") (pintype "input"))
      (node (ref "Y1") (pin "3") (pinfunction "2_3") (pintype "passive"))
    )
    (net (code "58") (name "Net-(IC2-XOUT)") (class "Default")
      (node (ref "IC2") (pin "21") (pinfunction "XOUT_21") (pintype "output"))
      (node (ref "R23") (pin "2") (pinfunction "2_2") (pintype "passive"))
    )
    (net (code "59") (name "Net-(L-PadA)") (class "Default")
      (node (ref "L") (pin "A") (pinfunction "A_A") (pintype "passive"))
      (node (ref "R11") (pin "2") (pinfunction "2_2") (pintype "passive"))
    )
    (net (code "60") (name "Net-(ON-PadA)") (class "Default")
      (node (ref "ON") (pin "A") (pinfunction "A_A") (pintype "passive"))
      (node (ref "R2") (pin "2") (pinfunction "2_2") (pintype "passive"))
    )
    (net (code "61") (name "Net-(SW1-P)") (class "Default")
      (node (ref "JP1") (pin "1") (pinfunction "1_1") (pintype "passive"))
      (node (ref "R7") (pin "1") (pinfunction "1_1") (pintype "passive"))
      (node (ref "SW1") (pin "B") (pinfunction "P_B") (pintype "passive"))
      (node (ref "T2") (pin "1") (pinfunction "G_1") (pintype "passive"))
    )
    (net (code "62") (name "Net-(T2-S)") (class "Default")
      (node (ref "D1") (pin "C") (pinfunction "C_C") (pintype "passive"))
      (node (ref "R7") (pin "2") (pinfunction "2_2") (pintype "passive"))
      (node (ref "T2") (pin "2") (pinfunction "S_2") (pintype "passive"))
    )
    (net (code "63") (name "Net-(TR1-G)") (class "Default")
      (node (ref "R1") (pin "1") (pinfunction "1_1") (pintype "passive"))
      (node (ref "R16") (pin "2") (pinfunction "2_2") (pintype "passive"))
      (node (ref "TR1") (pin "1") (pinfunction "G_1") (pintype "passive"))
    )
    (net (code "64") (name "VBUS") (class "Default")
      (node (ref "C5") (pin "2") (pinfunction "2_2") (pintype "passive"))
      (node (ref "C7") (pin "1") (pinfunction "1_1") (pintype "passive"))
      (node (ref "F2") (pin "2") (pinfunction "2_2") (pintype "passive"))
      (node (ref "TR1") (pin "3") (pinfunction "D_3") (pintype "passive"))
    )
    (net (code "65") (name "unconnected-(LED2-DO-Pad3)") (class "Default")
      (node (ref "LED2") (pin "3") (pinfunction "DO_3") (pintype "output"))
    )
    (net (code "66") (name "unconnected-(POWER-Pad1)") (class "Default")
      (node (ref "POWER") (pin "1") (pinfunction "1_1") (pintype "passive"))
    )
    (net (code "67") (name "unconnected-(SW1-S-PadC)") (class "Default")
      (node (ref "SW1") (pin "C") (pinfunction "S_C") (pintype "passive"))
    )
    (net (code "68") (name "unconnected-(SWD-SWO-Pad6)") (class "Default")
      (node (ref "SWD") (pin "6") (pinfunction "SWO_6") (pintype "bidirectional"))
    )
    (net (code "69") (name "unconnected-(SWD-TDI-Pad8)") (class "Default")
      (node (ref "SWD") (pin "8") (pinfunction "TDI_8") (pintype "bidirectional"))
    )
    (net (code "70") (name "unconnected-(U2-NC{slash}FB-Pad4)") (class "Default")
      (node (ref "U2") (pin "4") (pinfunction "NC/FB_4") (pintype "passive"))
    )
    (net (code "71") (name "unconnected-(X3-SBU1-PadA8)") (class "Default")
      (node (ref "X3") (pin "A8") (pinfunction "SBU1_A8") (pintype "bidirectional"))
    )
    (net (code "72") (name "unconnected-(X3-SBU2-PadB8)") (class "Default")
      (node (ref "X3") (pin "B8") (pinfunction "SBU2_B8") (pintype "bidirectional"))
    )
  )
)
